# Sheet1.net
KiCad netlist of a schematic drawn in Altium Designer
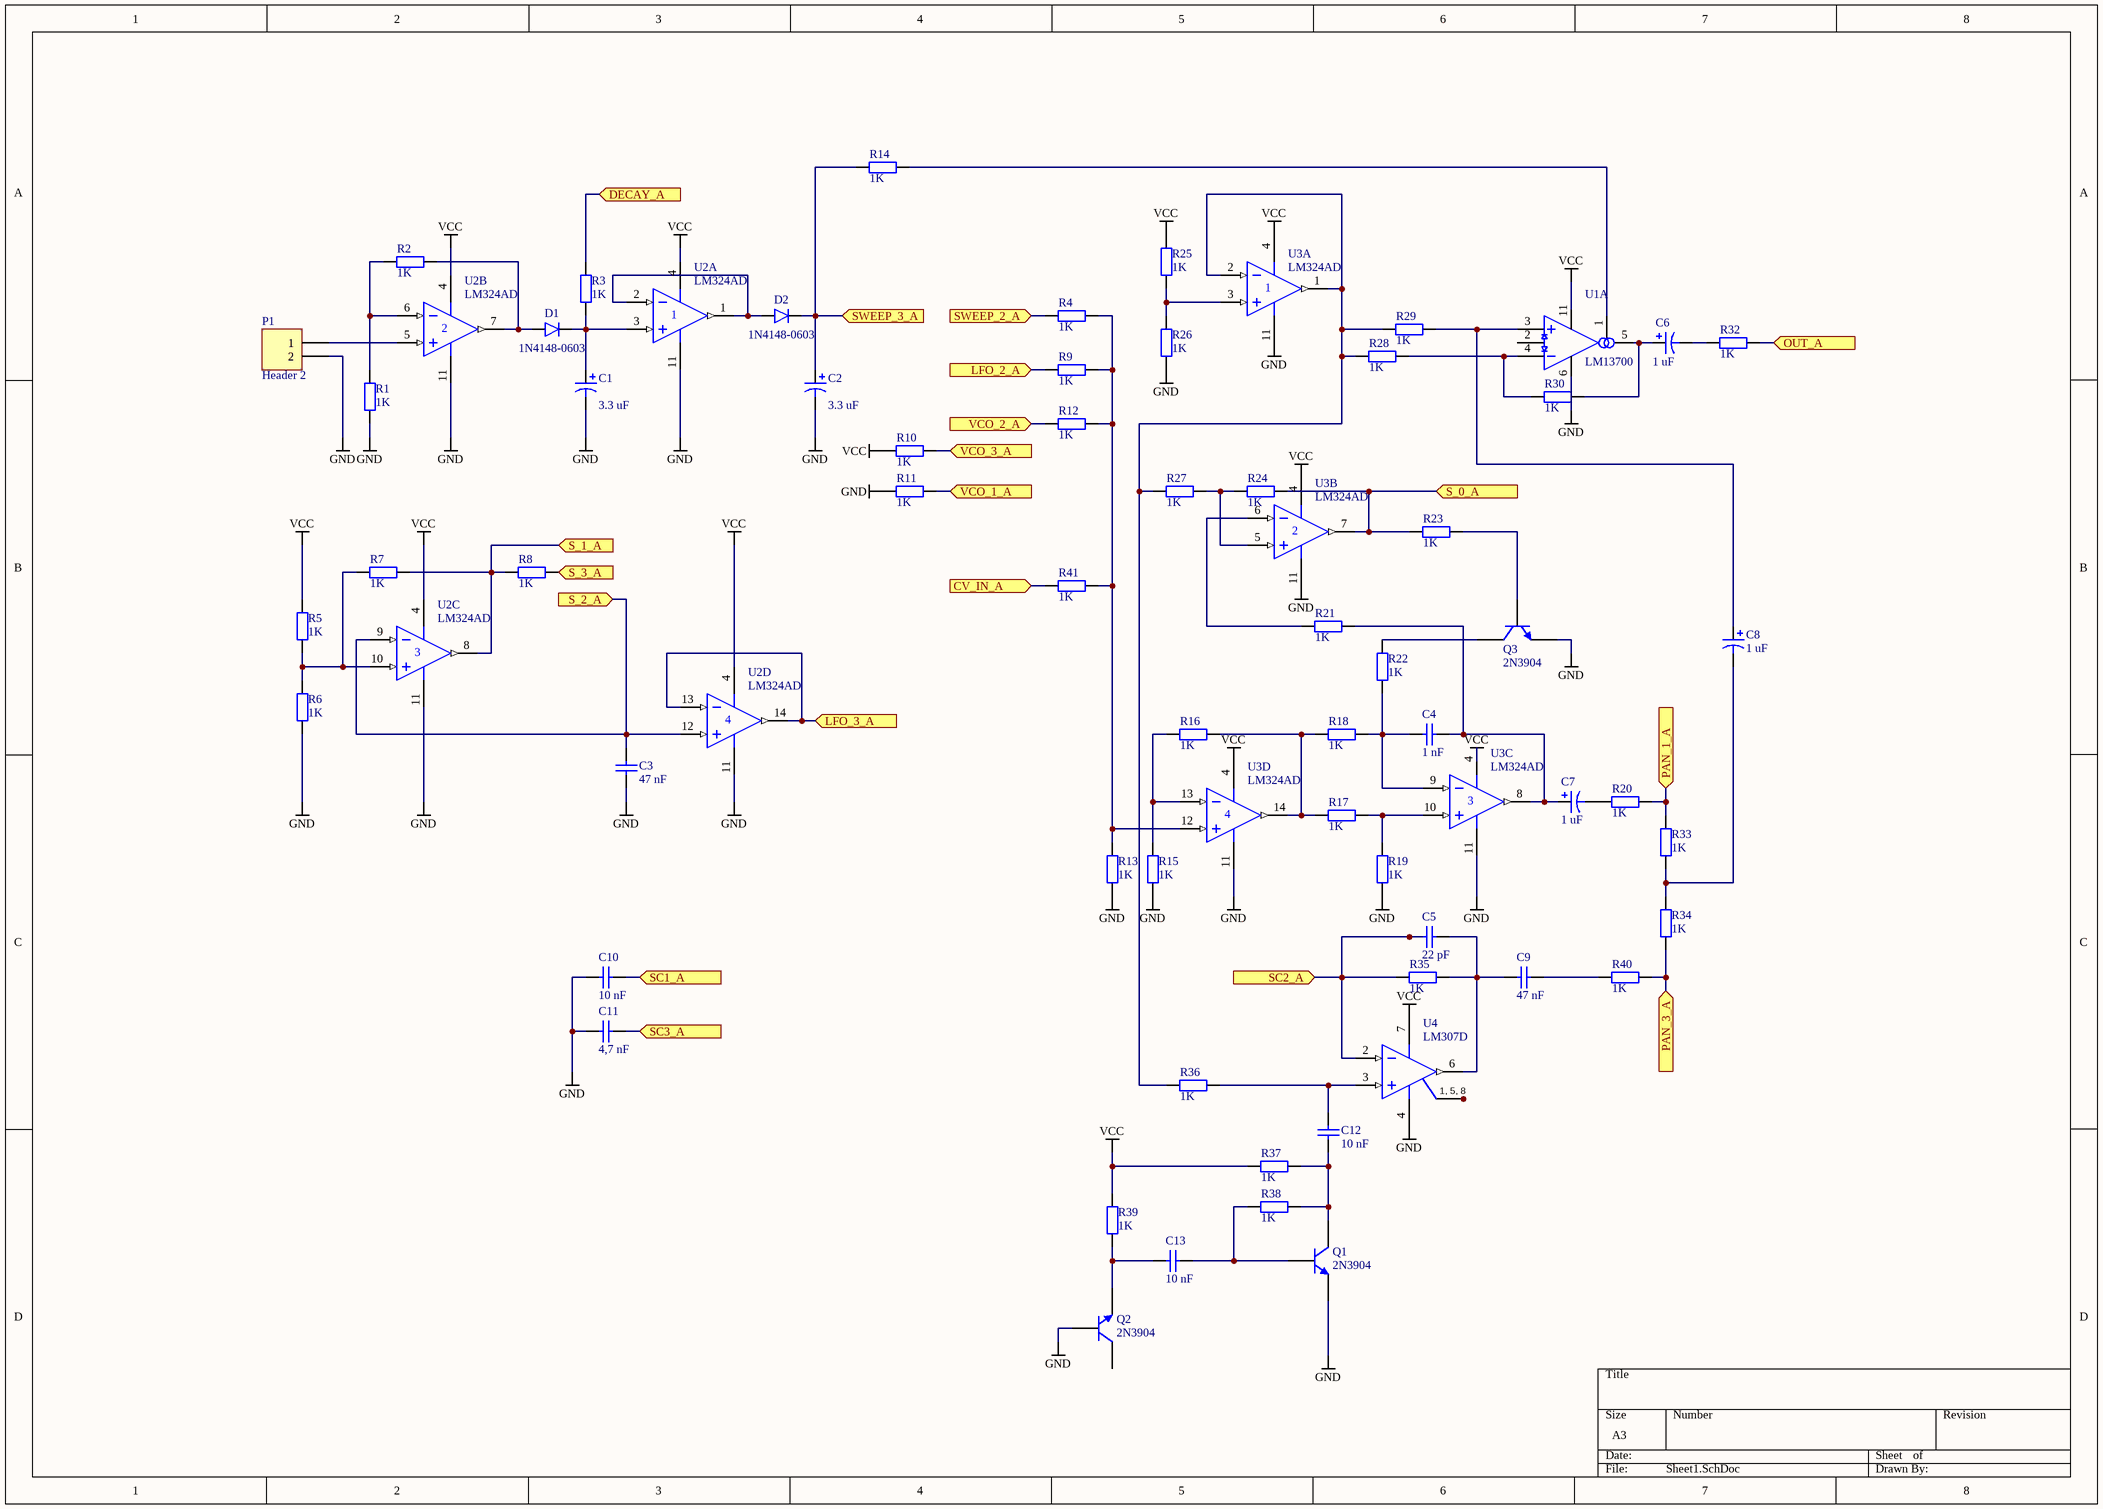
[diagram p0: Sheet1.SchDoc]

(export (version "E")
  (design (tool "Eeschema 10.0.6"))
  (components
    (comp (ref "C1")
      (value "3.3 uF")
      (footprint "C1206")
      (description "Polarized Capacitor (Radial)")
      (fields (field (name "Comment") "Cap Pol1") (field (name "PUBLISHER") "Altium Limited"))
      (libsource (lib "Miscellaneous Devices") (part "Cap Pol1"))
    )
    (comp (ref "C2")
      (value "3.3 uF")
      (footprint "C1206")
      (description "Polarized Capacitor (Radial)")
      (fields (field (name "Comment") "Cap Pol1") (field (name "PUBLISHER") "Altium Limited"))
      (libsource (lib "Miscellaneous Devices") (part "Cap Pol1"))
    )
    (comp (ref "C3")
      (value "47 nF")
      (footprint "C1206")
      (description "Capacitor")
      (fields (field (name "Comment") "Cap") (field (name "PUBLISHER") "Altium Limited"))
      (libsource (lib "Miscellaneous Devices") (part "Cap"))
    )
    (comp (ref "C4")
      (value "1 nF")
      (footprint "C1206")
      (description "Capacitor")
      (fields (field (name "Comment") "Cap") (field (name "PUBLISHER") "Altium Limited"))
      (libsource (lib "Miscellaneous Devices") (part "Cap"))
    )
    (comp (ref "C5")
      (value "22 pF")
      (footprint "C1206")
      (description "Capacitor")
      (fields (field (name "Comment") "Cap") (field (name "PUBLISHER") "Altium Limited"))
      (libsource (lib "Miscellaneous Devices") (part "Cap"))
    )
    (comp (ref "C6")
      (value "1 uF")
      (footprint "C1206")
      (description "Polarized Capacitor (Radial)")
      (fields (field (name "Comment") "Cap Pol1") (field (name "PUBLISHER") "Altium Limited"))
      (libsource (lib "Miscellaneous Devices") (part "Cap Pol1"))
    )
    (comp (ref "C7")
      (value "1 uF")
      (footprint "C1206")
      (description "Polarized Capacitor (Radial)")
      (fields (field (name "Comment") "Cap Pol1") (field (name "PUBLISHER") "Altium Limited"))
      (libsource (lib "Miscellaneous Devices") (part "Cap Pol1"))
    )
    (comp (ref "C8")
      (value "1 uF")
      (footprint "C1206")
      (description "Polarized Capacitor (Radial)")
      (fields (field (name "Comment") "Cap Pol1") (field (name "PUBLISHER") "Altium Limited"))
      (libsource (lib "Miscellaneous Devices") (part "Cap Pol1"))
    )
    (comp (ref "C9")
      (value "47 nF")
      (footprint "C1206")
      (description "Capacitor")
      (fields (field (name "Comment") "Cap") (field (name "PUBLISHER") "Altium Limited"))
      (libsource (lib "Miscellaneous Devices") (part "Cap"))
    )
    (comp (ref "C10")
      (value "10 nF")
      (footprint "C1206")
      (description "Capacitor")
      (fields (field (name "Comment") "Cap") (field (name "PUBLISHER") "Altium Limited"))
      (libsource (lib "Miscellaneous Devices") (part "Cap"))
    )
    (comp (ref "C11")
      (value "4,7 nF")
      (footprint "C1206")
      (description "Capacitor")
      (fields (field (name "Comment") "Cap") (field (name "PUBLISHER") "Altium Limited"))
      (libsource (lib "Miscellaneous Devices") (part "Cap"))
    )
    (comp (ref "C12")
      (value "10 nF")
      (footprint "C1206")
      (description "Capacitor")
      (fields (field (name "Comment") "Cap") (field (name "PUBLISHER") "Altium Limited"))
      (libsource (lib "Miscellaneous Devices") (part "Cap"))
    )
    (comp (ref "C13")
      (value "10 nF")
      (footprint "C1206")
      (description "Capacitor")
      (fields (field (name "Comment") "Cap") (field (name "PUBLISHER") "Altium Limited"))
      (libsource (lib "Miscellaneous Devices") (part "Cap"))
    )
    (comp (ref "D1")
      (value "1N4148-0603")
      (footprint "D0603")
      (description "Dioda: przełączająca; SMD; 100V; 150mA; 4ns; 0603")
      (libsource (lib "Component Library 3.0") (part "1N4148"))
    )
    (comp (ref "D2")
      (value "1N4148-0603")
      (footprint "D0603")
      (description "Dioda: przełączająca; SMD; 100V; 150mA; 4ns; 0603")
      (libsource (lib "Component Library 3.0") (part "1N4148"))
    )
    (comp (ref "P1")
      (value "Header 2")
      (footprint "HDR1X2")
      (description "Header, 2-Pin")
      (fields (field (name "PUBLISHER") "Altium Limited"))
      (libsource (lib "Miscellaneous Connectors") (part "Header 2"))
    )
    (comp (ref "Q1")
      (value "2N3904")
      (footprint "TO-92A")
      (description "NPN General Purpose Amplifier")
      (fields (field (name "PUBLISHER") "Altium Limited"))
      (libsource (lib "Miscellaneous Devices") (part "2N3904"))
    )
    (comp (ref "Q2")
      (value "2N3904")
      (footprint "TO-92A")
      (description "NPN General Purpose Amplifier")
      (fields (field (name "PUBLISHER") "Altium Limited"))
      (libsource (lib "Miscellaneous Devices") (part "2N3904"))
    )
    (comp (ref "Q3")
      (value "2N3904")
      (footprint "TO-92A")
      (description "NPN General Purpose Amplifier")
      (fields (field (name "PUBLISHER") "Altium Limited"))
      (libsource (lib "Miscellaneous Devices") (part "2N3904"))
    )
    (comp (ref "R1")
      (value "1K")
      (footprint "R1206")
      (description "Resistor")
      (fields (field (name "Comment") "Res2") (field (name "PUBLISHER") "Altium Limited"))
      (libsource (lib "") (part "Res2_3"))
    )
    (comp (ref "R2")
      (value "1K")
      (footprint "R1206")
      (description "Resistor")
      (fields (field (name "Comment") "Res2") (field (name "PUBLISHER") "Altium Limited"))
      (libsource (lib "") (part "Res2_2"))
    )
    (comp (ref "R3")
      (value "1K")
      (footprint "R1206")
      (description "Resistor")
      (fields (field (name "Comment") "Res2") (field (name "PUBLISHER") "Altium Limited"))
      (libsource (lib "Miscellaneous Devices") (part "Res2"))
    )
    (comp (ref "R4")
      (value "1K")
      (footprint "R1206")
      (description "Resistor")
      (fields (field (name "Comment") "Res2") (field (name "PUBLISHER") "Altium Limited"))
      (libsource (lib "") (part "Res2_1"))
    )
    (comp (ref "R5")
      (value "1K")
      (footprint "R1206")
      (description "Resistor")
      (fields (field (name "Comment") "Res2") (field (name "PUBLISHER") "Altium Limited"))
      (libsource (lib "") (part "Res2_3"))
    )
    (comp (ref "R6")
      (value "1K")
      (footprint "R1206")
      (description "Resistor")
      (fields (field (name "Comment") "Res2") (field (name "PUBLISHER") "Altium Limited"))
      (libsource (lib "") (part "Res2_3"))
    )
    (comp (ref "R7")
      (value "1K")
      (footprint "R1206")
      (description "Resistor")
      (fields (field (name "Comment") "Res2") (field (name "PUBLISHER") "Altium Limited"))
      (libsource (lib "") (part "Res2_2"))
    )
    (comp (ref "R8")
      (value "1K")
      (footprint "R1206")
      (description "Resistor")
      (fields (field (name "Comment") "Res2") (field (name "PUBLISHER") "Altium Limited"))
      (libsource (lib "") (part "Res2_2"))
    )
    (comp (ref "R9")
      (value "1K")
      (footprint "R1206")
      (description "Resistor")
      (fields (field (name "Comment") "Res2") (field (name "PUBLISHER") "Altium Limited"))
      (libsource (lib "") (part "Res2_2"))
    )
    (comp (ref "R10")
      (value "1K")
      (footprint "R1206")
      (description "Resistor")
      (fields (field (name "Comment") "Res2") (field (name "PUBLISHER") "Altium Limited"))
      (libsource (lib "") (part "Res2_1"))
    )
    (comp (ref "R11")
      (value "1K")
      (footprint "R1206")
      (description "Resistor")
      (fields (field (name "Comment") "Res2") (field (name "PUBLISHER") "Altium Limited"))
      (libsource (lib "") (part "Res2_2"))
    )
    (comp (ref "R12")
      (value "1K")
      (footprint "R1206")
      (description "Resistor")
      (fields (field (name "Comment") "Res2") (field (name "PUBLISHER") "Altium Limited"))
      (libsource (lib "") (part "Res2_2"))
    )
    (comp (ref "R13")
      (value "1K")
      (footprint "R1206")
      (description "Resistor")
      (fields (field (name "Comment") "Res2") (field (name "PUBLISHER") "Altium Limited"))
      (libsource (lib "Miscellaneous Devices") (part "Res2"))
    )
    (comp (ref "R14")
      (value "1K")
      (footprint "R1206")
      (description "Resistor")
      (fields (field (name "Comment") "Res2") (field (name "PUBLISHER") "Altium Limited"))
      (libsource (lib "") (part "Res2_1"))
    )
    (comp (ref "R15")
      (value "1K")
      (footprint "R1206")
      (description "Resistor")
      (fields (field (name "Comment") "Res2") (field (name "PUBLISHER") "Altium Limited"))
      (libsource (lib "") (part "Res2_3"))
    )
    (comp (ref "R16")
      (value "1K")
      (footprint "R1206")
      (description "Resistor")
      (fields (field (name "Comment") "Res2") (field (name "PUBLISHER") "Altium Limited"))
      (libsource (lib "") (part "Res2_2"))
    )
    (comp (ref "R17")
      (value "1K")
      (footprint "R1206")
      (description "Resistor")
      (fields (field (name "Comment") "Res2") (field (name "PUBLISHER") "Altium Limited"))
      (libsource (lib "") (part "Res2_2"))
    )
    (comp (ref "R18")
      (value "1K")
      (footprint "R1206")
      (description "Resistor")
      (fields (field (name "Comment") "Res2") (field (name "PUBLISHER") "Altium Limited"))
      (libsource (lib "") (part "Res2_2"))
    )
    (comp (ref "R19")
      (value "1K")
      (footprint "R1206")
      (description "Resistor")
      (fields (field (name "Comment") "Res2") (field (name "PUBLISHER") "Altium Limited"))
      (libsource (lib "Miscellaneous Devices") (part "Res2"))
    )
    (comp (ref "R20")
      (value "1K")
      (footprint "R1206")
      (description "Resistor")
      (fields (field (name "Comment") "Res2") (field (name "PUBLISHER") "Altium Limited"))
      (libsource (lib "") (part "Res2_1"))
    )
    (comp (ref "R21")
      (value "1K")
      (footprint "R1206")
      (description "Resistor")
      (fields (field (name "Comment") "Res2") (field (name "PUBLISHER") "Altium Limited"))
      (libsource (lib "") (part "Res2_1"))
    )
    (comp (ref "R22")
      (value "1K")
      (footprint "R1206")
      (description "Resistor")
      (fields (field (name "Comment") "Res2") (field (name "PUBLISHER") "Altium Limited"))
      (libsource (lib "") (part "Res2_3"))
    )
    (comp (ref "R23")
      (value "1K")
      (footprint "R1206")
      (description "Resistor")
      (fields (field (name "Comment") "Res2") (field (name "PUBLISHER") "Altium Limited"))
      (libsource (lib "") (part "Res2_2"))
    )
    (comp (ref "R24")
      (value "1K")
      (footprint "R1206")
      (description "Resistor")
      (fields (field (name "Comment") "Res2") (field (name "PUBLISHER") "Altium Limited"))
      (libsource (lib "") (part "Res2_2"))
    )
    (comp (ref "R25")
      (value "1K")
      (footprint "R1206")
      (description "Resistor")
      (fields (field (name "Comment") "Res2") (field (name "PUBLISHER") "Altium Limited"))
      (libsource (lib "Miscellaneous Devices") (part "Res2"))
    )
    (comp (ref "R26")
      (value "1K")
      (footprint "R1206")
      (description "Resistor")
      (fields (field (name "Comment") "Res2") (field (name "PUBLISHER") "Altium Limited"))
      (libsource (lib "Miscellaneous Devices") (part "Res2"))
    )
    (comp (ref "R27")
      (value "1K")
      (footprint "R1206")
      (description "Resistor")
      (fields (field (name "Comment") "Res2") (field (name "PUBLISHER") "Altium Limited"))
      (libsource (lib "") (part "Res2_1"))
    )
    (comp (ref "R28")
      (value "1K")
      (footprint "R1206")
      (description "Resistor")
      (fields (field (name "Comment") "Res2") (field (name "PUBLISHER") "Altium Limited"))
      (libsource (lib "") (part "Res2_1"))
    )
    (comp (ref "R29")
      (value "1K")
      (footprint "R1206")
      (description "Resistor")
      (fields (field (name "Comment") "Res2") (field (name "PUBLISHER") "Altium Limited"))
      (libsource (lib "") (part "Res2_1"))
    )
    (comp (ref "R30")
      (value "1K")
      (footprint "R1206")
      (description "Resistor")
      (fields (field (name "Comment") "Res2") (field (name "PUBLISHER") "Altium Limited"))
      (libsource (lib "") (part "Res2_1"))
    )
    (comp (ref "R32")
      (value "1K")
      (footprint "R1206")
      (description "Resistor")
      (fields (field (name "Comment") "Res2") (field (name "PUBLISHER") "Altium Limited"))
      (libsource (lib "") (part "Res2_1"))
    )
    (comp (ref "R33")
      (value "1K")
      (footprint "R1206")
      (description "Resistor")
      (fields (field (name "Comment") "Res2") (field (name "PUBLISHER") "Altium Limited"))
      (libsource (lib "") (part "Res2_3"))
    )
    (comp (ref "R34")
      (value "1K")
      (footprint "R1206")
      (description "Resistor")
      (fields (field (name "Comment") "Res2") (field (name "PUBLISHER") "Altium Limited"))
      (libsource (lib "") (part "Res2_3"))
    )
    (comp (ref "R35")
      (value "1K")
      (footprint "R1206")
      (description "Resistor")
      (fields (field (name "Comment") "Res2") (field (name "PUBLISHER") "Altium Limited"))
      (libsource (lib "") (part "Res2_2"))
    )
    (comp (ref "R36")
      (value "1K")
      (footprint "R1206")
      (description "Resistor")
      (fields (field (name "Comment") "Res2") (field (name "PUBLISHER") "Altium Limited"))
      (libsource (lib "") (part "Res2_2"))
    )
    (comp (ref "R37")
      (value "1K")
      (footprint "R1206")
      (description "Resistor")
      (fields (field (name "Comment") "Res2") (field (name "PUBLISHER") "Altium Limited"))
      (libsource (lib "") (part "Res2_2"))
    )
    (comp (ref "R38")
      (value "1K")
      (footprint "R1206")
      (description "Resistor")
      (fields (field (name "Comment") "Res2") (field (name "PUBLISHER") "Altium Limited"))
      (libsource (lib "") (part "Res2_2"))
    )
    (comp (ref "R39")
      (value "1K")
      (footprint "R1206")
      (description "Resistor")
      (fields (field (name "Comment") "Res2") (field (name "PUBLISHER") "Altium Limited"))
      (libsource (lib "Miscellaneous Devices") (part "Res2"))
    )
    (comp (ref "R40")
      (value "1K")
      (footprint "R1206")
      (description "Resistor")
      (fields (field (name "Comment") "Res2") (field (name "PUBLISHER") "Altium Limited"))
      (libsource (lib "") (part "Res2_1"))
    )
    (comp (ref "R41")
      (value "1K")
      (footprint "R1206")
      (description "Resistor")
      (fields (field (name "Comment") "Res2") (field (name "PUBLISHER") "Altium Limited"))
      (libsource (lib "") (part "Res2_1"))
    )
    (comp (ref "U1") (value "LM13700") (footprint "SOIC16") (libsource (lib "Schlib1") (part "LM13700")))
    (comp (ref "U2")
      (value "LM324AD")
      (footprint "D014_N")
      (description "Quadruple Operational Amplifier")
      (fields (field (name "PUBLISHER") "Altium Limited"))
      (libsource (lib "TI Operational Amplifier") (part "LM324AD"))
    )
    (comp (ref "U3")
      (value "LM324AD")
      (footprint "D014_N")
      (description "Quadruple Operational Amplifier")
      (fields (field (name "PUBLISHER") "Altium Limited"))
      (libsource (lib "TI Operational Amplifier") (part "LM324AD"))
    )
    (comp (ref "U4")
      (value "LM307D")
      (footprint "D008_L")
      (description "High-Performance Operational Amplifier")
      (fields (field (name "PUBLISHER") "Altium Limited"))
      (libsource (lib "TI Operational Amplifier") (part "LM307D"))
    )
  )
  (nets
    (net (code "1") (name "/CV_IN_A") (class "Default")
      (node (ref "R41") (pin "1") (pinfunction "1_1") (pintype "passive"))
    )
    (net (code "2") (name "/DECAY_A") (class "Default")
      (node (ref "R3") (pin "1") (pinfunction "1_1") (pintype "passive"))
    )
    (net (code "3") (name "/LFO_2_A") (class "Default")
      (node (ref "R9") (pin "2") (pinfunction "2_2") (pintype "passive"))
    )
    (net (code "4") (name "/LFO_3_A") (class "Default")
      (node (ref "U2") (pin "13") (pinfunction "IN-_13") (pintype "input"))
      (node (ref "U2") (pin "14") (pinfunction "OUT_14") (pintype "output"))
    )
    (net (code "5") (name "/OUT_A") (class "Default")
      (node (ref "R32") (pin "2") (pinfunction "2_2") (pintype "passive"))
    )
    (net (code "6") (name "/PAN_1_A") (class "Default")
      (node (ref "R20") (pin "2") (pinfunction "2_2") (pintype "passive"))
      (node (ref "R33") (pin "2") (pinfunction "2_2") (pintype "passive"))
    )
    (net (code "7") (name "/PAN_3_A") (class "Default")
      (node (ref "R34") (pin "1") (pinfunction "1_1") (pintype "passive"))
      (node (ref "R40") (pin "2") (pinfunction "2_2") (pintype "passive"))
    )
    (net (code "8") (name "/SC1_A") (class "Default")
      (node (ref "C10") (pin "1") (pinfunction "1_1") (pintype "passive"))
    )
    (net (code "9") (name "/SC2_A") (class "Default")
      (node (ref "C5") (pin "2") (pinfunction "2_2") (pintype "passive"))
      (node (ref "R35") (pin "2") (pinfunction "2_2") (pintype "passive"))
      (node (ref "U4") (pin "2") (pinfunction "IN-_2") (pintype "input"))
    )
    (net (code "10") (name "/SC3_A") (class "Default")
      (node (ref "C11") (pin "1") (pinfunction "1_1") (pintype "passive"))
    )
    (net (code "11") (name "/SWEEP_2_A") (class "Default")
      (node (ref "R4") (pin "1") (pinfunction "1_1") (pintype "passive"))
    )
    (net (code "12") (name "/SWEEP_3_A") (class "Default")
      (node (ref "C2") (pin "1") (pinfunction "1_1") (pintype "passive"))
      (node (ref "D2") (pin "1") (pinfunction "1_1") (pintype "passive"))
      (node (ref "R14") (pin "1") (pinfunction "1_1") (pintype "passive"))
    )
    (net (code "13") (name "/S_0_A") (class "Default")
      (node (ref "R23") (pin "2") (pinfunction "2_2") (pintype "passive"))
      (node (ref "R24") (pin "1") (pinfunction "1_1") (pintype "passive"))
      (node (ref "U3") (pin "7") (pinfunction "OUT_7") (pintype "output"))
    )
    (net (code "14") (name "/S_1_A") (class "Default")
      (node (ref "R7") (pin "1") (pinfunction "1_1") (pintype "passive"))
      (node (ref "R8") (pin "2") (pinfunction "2_2") (pintype "passive"))
      (node (ref "U2") (pin "8") (pinfunction "OUT_8") (pintype "output"))
    )
    (net (code "15") (name "/S_2_A") (class "Default")
      (node (ref "C3") (pin "2") (pinfunction "2_2") (pintype "passive"))
      (node (ref "U2") (pin "12") (pinfunction "IN+_12") (pintype "input"))
      (node (ref "U2") (pin "9") (pinfunction "IN-_9") (pintype "input"))
    )
    (net (code "16") (name "/S_3_A") (class "Default")
      (node (ref "R8") (pin "1") (pinfunction "1_1") (pintype "passive"))
    )
    (net (code "17") (name "/VCO_1_A") (class "Default")
      (node (ref "R11") (pin "1") (pinfunction "1_1") (pintype "passive"))
    )
    (net (code "18") (name "/VCO_2_A") (class "Default")
      (node (ref "R12") (pin "2") (pinfunction "2_2") (pintype "passive"))
    )
    (net (code "19") (name "/VCO_3_A") (class "Default")
      (node (ref "R10") (pin "2") (pinfunction "2_2") (pintype "passive"))
    )
    (net (code "20") (name "GND") (class "Default")
      (node (ref "C1") (pin "2") (pinfunction "2_2") (pintype "passive"))
      (node (ref "C10") (pin "2") (pinfunction "2_2") (pintype "passive"))
      (node (ref "C11") (pin "2") (pinfunction "2_2") (pintype "passive"))
      (node (ref "C2") (pin "2") (pinfunction "2_2") (pintype "passive"))
      (node (ref "C3") (pin "1") (pinfunction "1_1") (pintype "passive"))
      (node (ref "P1") (pin "2") (pinfunction "2_2") (pintype "passive"))
      (node (ref "Q1") (pin "1") (pinfunction "E_1") (pintype "passive"))
      (node (ref "Q2") (pin "2") (pinfunction "B_2") (pintype "passive"))
      (node (ref "Q3") (pin "1") (pinfunction "E_1") (pintype "passive"))
      (node (ref "R1") (pin "1") (pinfunction "1_1") (pintype "passive"))
      (node (ref "R11") (pin "2") (pinfunction "2_2") (pintype "passive"))
      (node (ref "R13") (pin "2") (pinfunction "2_2") (pintype "passive"))
      (node (ref "R15") (pin "1") (pinfunction "1_1") (pintype "passive"))
      (node (ref "R19") (pin "2") (pinfunction "2_2") (pintype "passive"))
      (node (ref "R26") (pin "2") (pinfunction "2_2") (pintype "passive"))
      (node (ref "R6") (pin "1") (pinfunction "1_1") (pintype "passive"))
      (node (ref "U1") (pin "6") (pinfunction "V-_6") (pintype "passive"))
      (node (ref "U2") (pin "11") (pinfunction "V-_11") (pintype "power_in"))
      (node (ref "U3") (pin "11") (pinfunction "V-_11") (pintype "power_in"))
      (node (ref "U4") (pin "4") (pinfunction "V-_4") (pintype "power_in"))
    )
    (net (code "21") (name "Net-(C6-Pad1)") (class "Default")
      (node (ref "C6") (pin "1") (pinfunction "1_1") (pintype "passive"))
      (node (ref "R30") (pin "2") (pinfunction "2_2") (pintype "passive"))
      (node (ref "U1") (pin "5") (pinfunction "amp_bias_5") (pintype "passive"))
    )
    (net (code "22") (name "Net-(C6-Pad2)") (class "Default")
      (node (ref "C6") (pin "2") (pinfunction "2_2") (pintype "passive"))
      (node (ref "R32") (pin "1") (pinfunction "1_1") (pintype "passive"))
    )
    (net (code "23") (name "Net-(C7-Pad2)") (class "Default")
      (node (ref "C7") (pin "2") (pinfunction "2_2") (pintype "passive"))
      (node (ref "R20") (pin "1") (pinfunction "1_1") (pintype "passive"))
    )
    (net (code "24") (name "Net-(C8-Pad2)") (class "Default")
      (node (ref "C8") (pin "2") (pinfunction "2_2") (pintype "passive"))
      (node (ref "R33") (pin "1") (pinfunction "1_1") (pintype "passive"))
      (node (ref "R34") (pin "2") (pinfunction "2_2") (pintype "passive"))
    )
    (net (code "25") (name "Net-(C9-Pad2)") (class "Default")
      (node (ref "C9") (pin "2") (pinfunction "2_2") (pintype "passive"))
      (node (ref "R40") (pin "1") (pinfunction "1_1") (pintype "passive"))
    )
    (net (code "26") (name "Net-(Q1-B)") (class "Default")
      (node (ref "C13") (pin "2") (pinfunction "2_2") (pintype "passive"))
      (node (ref "Q1") (pin "2") (pinfunction "B_2") (pintype "passive"))
      (node (ref "R38") (pin "2") (pinfunction "2_2") (pintype "passive"))
    )
    (net (code "27") (name "Net-(Q1-C)") (class "Default")
      (node (ref "C12") (pin "2") (pinfunction "2_2") (pintype "passive"))
      (node (ref "Q1") (pin "3") (pinfunction "C_3") (pintype "passive"))
      (node (ref "R37") (pin "1") (pinfunction "1_1") (pintype "passive"))
      (node (ref "R38") (pin "1") (pinfunction "1_1") (pintype "passive"))
    )
    (net (code "28") (name "Net-(Q2-E)") (class "Default")
      (node (ref "C13") (pin "1") (pinfunction "1_1") (pintype "passive"))
      (node (ref "Q2") (pin "1") (pinfunction "E_1") (pintype "passive"))
      (node (ref "R39") (pin "2") (pinfunction "2_2") (pintype "passive"))
    )
    (net (code "29") (name "Net-(Q3-B)") (class "Default")
      (node (ref "Q3") (pin "2") (pinfunction "B_2") (pintype "passive"))
      (node (ref "R23") (pin "1") (pinfunction "1_1") (pintype "passive"))
    )
    (net (code "30") (name "Net-(Q3-C)") (class "Default")
      (node (ref "Q3") (pin "3") (pinfunction "C_3") (pintype "passive"))
      (node (ref "R22") (pin "2") (pinfunction "2_2") (pintype "passive"))
    )
    (net (code "31") (name "Net-(R14-Pad2)") (class "Default")
      (node (ref "R14") (pin "2") (pinfunction "2_2") (pintype "passive"))
      (node (ref "U1") (pin "1") (pinfunction "amp_bias_1") (pintype "passive"))
    )
    (net (code "32") (name "Net-(R28-Pad2)") (class "Default")
      (node (ref "R28") (pin "2") (pinfunction "2_2") (pintype "passive"))
      (node (ref "R30") (pin "1") (pinfunction "1_1") (pintype "passive"))
      (node (ref "U1") (pin "4") (pinfunction "amp_bias_4") (pintype "passive"))
    )
    (net (code "33") (name "Net-(U1A-+)") (class "Default")
      (node (ref "C8") (pin "1") (pinfunction "1_1") (pintype "passive"))
      (node (ref "R29") (pin "2") (pinfunction "2_2") (pintype "passive"))
      (node (ref "U1") (pin "3") (pinfunction "+_3") (pintype "passive"))
    )
    (net (code "34") (name "Net-(U2A-IN+)") (class "Default")
      (node (ref "C1") (pin "1") (pinfunction "1_1") (pintype "passive"))
      (node (ref "D1") (pin "1") (pinfunction "1_1") (pintype "passive"))
      (node (ref "R3") (pin "2") (pinfunction "2_2") (pintype "passive"))
      (node (ref "U2") (pin "3") (pinfunction "IN+_3") (pintype "input"))
    )
    (net (code "35") (name "Net-(U2A-IN-)") (class "Default")
      (node (ref "D2") (pin "2") (pinfunction "2_2") (pintype "passive"))
      (node (ref "U2") (pin "1") (pinfunction "OUT_1") (pintype "output"))
      (node (ref "U2") (pin "2") (pinfunction "IN-_2") (pintype "input"))
    )
    (net (code "36") (name "Net-(U2B-IN+)") (class "Default")
      (node (ref "P1") (pin "1") (pinfunction "1_1") (pintype "passive"))
      (node (ref "U2") (pin "5") (pinfunction "IN+_5") (pintype "input"))
    )
    (net (code "37") (name "Net-(U2B-IN-)") (class "Default")
      (node (ref "R1") (pin "2") (pinfunction "2_2") (pintype "passive"))
      (node (ref "R2") (pin "2") (pinfunction "2_2") (pintype "passive"))
      (node (ref "U2") (pin "6") (pinfunction "IN-_6") (pintype "input"))
    )
    (net (code "38") (name "Net-(U2B-OUT)") (class "Default")
      (node (ref "D1") (pin "2") (pinfunction "2_2") (pintype "passive"))
      (node (ref "R2") (pin "1") (pinfunction "1_1") (pintype "passive"))
      (node (ref "U2") (pin "7") (pinfunction "OUT_7") (pintype "output"))
    )
    (net (code "39") (name "Net-(U2C-IN+)") (class "Default")
      (node (ref "R5") (pin "1") (pinfunction "1_1") (pintype "passive"))
      (node (ref "R6") (pin "2") (pinfunction "2_2") (pintype "passive"))
      (node (ref "R7") (pin "2") (pinfunction "2_2") (pintype "passive"))
      (node (ref "U2") (pin "10") (pinfunction "IN+_10") (pintype "input"))
    )
    (net (code "40") (name "Net-(U3A-IN+)") (class "Default")
      (node (ref "R25") (pin "2") (pinfunction "2_2") (pintype "passive"))
      (node (ref "R26") (pin "1") (pinfunction "1_1") (pintype "passive"))
      (node (ref "U3") (pin "3") (pinfunction "IN+_3") (pintype "input"))
    )
    (net (code "41") (name "Net-(U3A-IN-)") (class "Default")
      (node (ref "R27") (pin "1") (pinfunction "1_1") (pintype "passive"))
      (node (ref "R28") (pin "1") (pinfunction "1_1") (pintype "passive"))
      (node (ref "R29") (pin "1") (pinfunction "1_1") (pintype "passive"))
      (node (ref "R36") (pin "2") (pinfunction "2_2") (pintype "passive"))
      (node (ref "U3") (pin "1") (pinfunction "OUT_1") (pintype "output"))
      (node (ref "U3") (pin "2") (pinfunction "IN-_2") (pintype "input"))
    )
    (net (code "42") (name "Net-(U3B-IN+)") (class "Default")
      (node (ref "R24") (pin "2") (pinfunction "2_2") (pintype "passive"))
      (node (ref "R27") (pin "2") (pinfunction "2_2") (pintype "passive"))
      (node (ref "U3") (pin "5") (pinfunction "IN+_5") (pintype "input"))
    )
    (net (code "43") (name "Net-(U3B-IN-)") (class "Default")
      (node (ref "R21") (pin "1") (pinfunction "1_1") (pintype "passive"))
      (node (ref "U3") (pin "6") (pinfunction "IN-_6") (pintype "input"))
    )
    (net (code "44") (name "Net-(U3C-IN+)") (class "Default")
      (node (ref "R17") (pin "1") (pinfunction "1_1") (pintype "passive"))
      (node (ref "R19") (pin "1") (pinfunction "1_1") (pintype "passive"))
      (node (ref "U3") (pin "10") (pinfunction "IN+_10") (pintype "input"))
    )
    (net (code "45") (name "Net-(U3C-IN-)") (class "Default")
      (node (ref "C4") (pin "2") (pinfunction "2_2") (pintype "passive"))
      (node (ref "R18") (pin "1") (pinfunction "1_1") (pintype "passive"))
      (node (ref "R22") (pin "1") (pinfunction "1_1") (pintype "passive"))
      (node (ref "U3") (pin "9") (pinfunction "IN-_9") (pintype "input"))
    )
    (net (code "46") (name "Net-(U3C-OUT)") (class "Default")
      (node (ref "C4") (pin "1") (pinfunction "1_1") (pintype "passive"))
      (node (ref "C7") (pin "1") (pinfunction "1_1") (pintype "passive"))
      (node (ref "R21") (pin "2") (pinfunction "2_2") (pintype "passive"))
      (node (ref "U3") (pin "8") (pinfunction "OUT_8") (pintype "output"))
    )
    (net (code "47") (name "Net-(U3D-IN+)") (class "Default")
      (node (ref "R12") (pin "1") (pinfunction "1_1") (pintype "passive"))
      (node (ref "R13") (pin "1") (pinfunction "1_1") (pintype "passive"))
      (node (ref "R4") (pin "2") (pinfunction "2_2") (pintype "passive"))
      (node (ref "R41") (pin "2") (pinfunction "2_2") (pintype "passive"))
      (node (ref "R9") (pin "1") (pinfunction "1_1") (pintype "passive"))
      (node (ref "U3") (pin "12") (pinfunction "IN+_12") (pintype "input"))
    )
    (net (code "48") (name "Net-(U3D-IN-)") (class "Default")
      (node (ref "R15") (pin "2") (pinfunction "2_2") (pintype "passive"))
      (node (ref "R16") (pin "2") (pinfunction "2_2") (pintype "passive"))
      (node (ref "U3") (pin "13") (pinfunction "IN-_13") (pintype "input"))
    )
    (net (code "49") (name "Net-(U3D-OUT)") (class "Default")
      (node (ref "R16") (pin "1") (pinfunction "1_1") (pintype "passive"))
      (node (ref "R17") (pin "2") (pinfunction "2_2") (pintype "passive"))
      (node (ref "R18") (pin "2") (pinfunction "2_2") (pintype "passive"))
      (node (ref "U3") (pin "14") (pinfunction "OUT_14") (pintype "output"))
    )
    (net (code "50") (name "Net-(U4-IN+)") (class "Default")
      (node (ref "C12") (pin "1") (pinfunction "1_1") (pintype "passive"))
      (node (ref "R36") (pin "1") (pinfunction "1_1") (pintype "passive"))
      (node (ref "U4") (pin "3") (pinfunction "IN+_3") (pintype "input"))
    )
    (net (code "51") (name "Net-(U4-NC-Pad1)") (class "Default")
      (node (ref "U4") (pin "1") (pinfunction "NC_1") (pintype "passive"))
      (node (ref "U4") (pin "5") (pinfunction "NC_5") (pintype "passive"))
      (node (ref "U4") (pin "8") (pinfunction "NC_8") (pintype "passive"))
    )
    (net (code "52") (name "Net-(U4-OUT)") (class "Default")
      (node (ref "C5") (pin "1") (pinfunction "1_1") (pintype "passive"))
      (node (ref "C9") (pin "1") (pinfunction "1_1") (pintype "passive"))
      (node (ref "R35") (pin "1") (pinfunction "1_1") (pintype "passive"))
      (node (ref "U4") (pin "6") (pinfunction "OUT_6") (pintype "output"))
    )
    (net (code "53") (name "VCC") (class "Default")
      (node (ref "R10") (pin "1") (pinfunction "1_1") (pintype "passive"))
      (node (ref "R25") (pin "1") (pinfunction "1_1") (pintype "passive"))
      (node (ref "R37") (pin "2") (pinfunction "2_2") (pintype "passive"))
      (node (ref "R39") (pin "1") (pinfunction "1_1") (pintype "passive"))
      (node (ref "R5") (pin "2") (pinfunction "2_2") (pintype "passive"))
      (node (ref "U1") (pin "11") (pinfunction "V+_11") (pintype "passive"))
      (node (ref "U2") (pin "4") (pinfunction "V+_4") (pintype "power_in"))
      (node (ref "U3") (pin "4") (pinfunction "V+_4") (pintype "power_in"))
      (node (ref "U4") (pin "7") (pinfunction "V+_7") (pintype "power_in"))
    )
    (net (code "54") (name "unconnected-(Q2-C-Pad3)") (class "Default")
      (node (ref "Q2") (pin "3") (pinfunction "C_3") (pintype "passive"))
    )
    (net (code "55") (name "unconnected-(U1A-amp_bias-Pad2)") (class "Default")
      (node (ref "U1") (pin "2") (pinfunction "amp_bias_2") (pintype "passive"))
    )
  )
)
